# SNES-GamePad.net
KiCad netlist of a schematic drawn in EAGLE
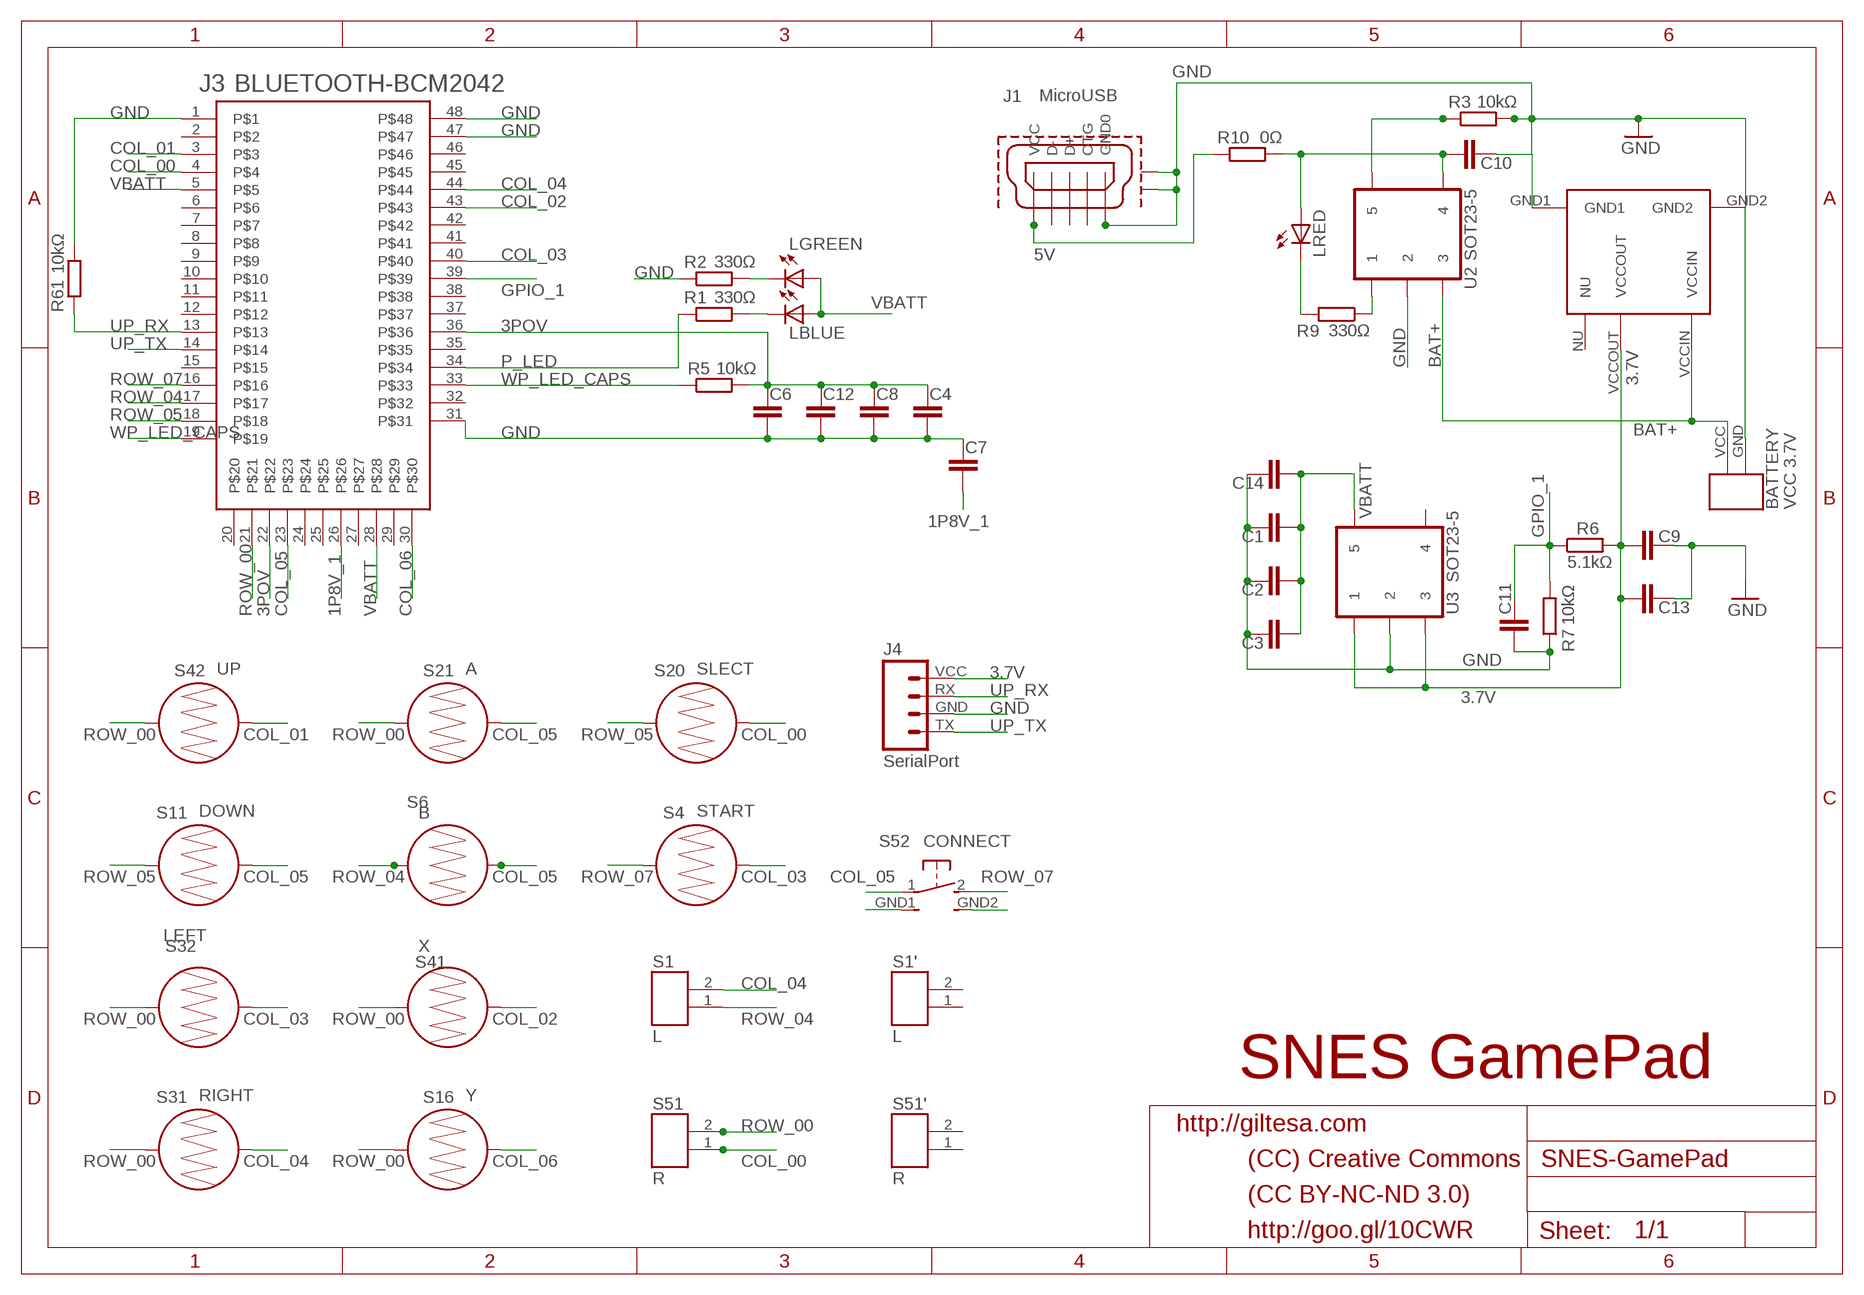
[diagram p0: schematic, sheet 1]

(export (version "E")
  (design (tool "Eeschema 10.0.6"))
  (components
    (comp (ref "BATTERY")
      (value "VCC 3.7V")
      (footprint "eagle-import:1X02_SMD_BIG")
      (libsource (lib "eagle-import") (part "1X02_SMD_BIG"))
    )
    (comp (ref "C1")
      (value "C-EUC0603")
      (footprint "eagle-import:C0603")
      (libsource (lib "eagle-import") (part "C-EUC0603"))
    )
    (comp (ref "C2")
      (value "C-EUC0805")
      (footprint "eagle-import:C0805")
      (libsource (lib "eagle-import") (part "C-EUC0805"))
    )
    (comp (ref "C3")
      (value "C-EUC0805")
      (footprint "eagle-import:C0805")
      (libsource (lib "eagle-import") (part "C-EUC0805"))
    )
    (comp (ref "C4")
      (value "C-EUC0603")
      (footprint "eagle-import:C0603")
      (libsource (lib "eagle-import") (part "C-EUC0603"))
    )
    (comp (ref "C6")
      (value "C-EUC0805")
      (footprint "eagle-import:C0805")
      (libsource (lib "eagle-import") (part "C-EUC0805"))
    )
    (comp (ref "C7")
      (value "C-EUC0805")
      (footprint "eagle-import:C0805")
      (libsource (lib "eagle-import") (part "C-EUC0805"))
    )
    (comp (ref "C8")
      (value "C-EUC0805")
      (footprint "eagle-import:C0805")
      (libsource (lib "eagle-import") (part "C-EUC0805"))
    )
    (comp (ref "C9")
      (value "C-EUC0805")
      (footprint "eagle-import:C0805")
      (libsource (lib "eagle-import") (part "C-EUC0805"))
    )
    (comp (ref "C10")
      (value "C-EUC0603")
      (footprint "eagle-import:C0603")
      (libsource (lib "eagle-import") (part "C-EUC0603"))
    )
    (comp (ref "C11")
      (value "C-EUC0603")
      (footprint "eagle-import:C0603")
      (libsource (lib "eagle-import") (part "C-EUC0603"))
    )
    (comp (ref "C12")
      (value "C-EUC0805")
      (footprint "eagle-import:C0805")
      (libsource (lib "eagle-import") (part "C-EUC0805"))
    )
    (comp (ref "C13")
      (value "C-EUC0805")
      (footprint "eagle-import:C0805")
      (libsource (lib "eagle-import") (part "C-EUC0805"))
    )
    (comp (ref "C14")
      (value "C-EUC0805")
      (footprint "eagle-import:C0805")
      (libsource (lib "eagle-import") (part "C-EUC0805"))
    )
    (comp (ref "J1")
      (value "MicroUSB")
      (footprint "eagle-import:MICRO_USB_1")
      (libsource (lib "eagle-import") (part "MICRO_USB_1"))
    )
    (comp (ref "J2")
      (value "INTERRUPTOR_1")
      (footprint "eagle-import:INTERRUPTOR_1")
      (libsource (lib "eagle-import") (part "INTERRUPTOR_1"))
    )
    (comp (ref "J3")
      (value "BLUETOOTH-BCM2042")
      (footprint "eagle-import:BLUETOOTH-BCM2042")
      (libsource (lib "eagle-import") (part "BLUETOOTH-BCM2042"))
    )
    (comp (ref "J4")
      (value "SerialPort")
      (footprint "eagle-import:ISP_PORT_SNES")
      (libsource (lib "eagle-import") (part "ISP_PORT_SNES"))
    )
    (comp (ref "LBLUE")
      (value "LEDCHIPLED_0805")
      (footprint "eagle-import:CHIPLED_0805")
      (libsource (lib "eagle-import") (part "LEDCHIPLED_0805"))
    )
    (comp (ref "LGREEN")
      (value "LEDCHIPLED_0805")
      (footprint "eagle-import:CHIPLED_0805")
      (libsource (lib "eagle-import") (part "LEDCHIPLED_0805"))
    )
    (comp (ref "LRED")
      (value "LEDCHIPLED_0805")
      (footprint "eagle-import:CHIPLED_0805")
      (libsource (lib "eagle-import") (part "LEDCHIPLED_0805"))
    )
    (comp (ref "R1")
      (value "330Ω")
      (footprint "eagle-import:R0603")
      (libsource (lib "eagle-import") (part "R-EU_R0603"))
    )
    (comp (ref "R2")
      (value "330Ω")
      (footprint "eagle-import:R0603")
      (libsource (lib "eagle-import") (part "R-EU_R0603"))
    )
    (comp (ref "R3")
      (value "10kΩ")
      (footprint "eagle-import:R0603")
      (libsource (lib "eagle-import") (part "R-EU_R0603"))
    )
    (comp (ref "R5")
      (value "10kΩ")
      (footprint "eagle-import:R0603")
      (libsource (lib "eagle-import") (part "R-EU_R0603"))
    )
    (comp (ref "R6")
      (value "5.1kΩ")
      (footprint "eagle-import:R0603")
      (libsource (lib "eagle-import") (part "R-EU_R0603"))
    )
    (comp (ref "R7")
      (value "10kΩ")
      (footprint "eagle-import:R0603")
      (libsource (lib "eagle-import") (part "R-EU_R0603"))
    )
    (comp (ref "R9")
      (value "330Ω")
      (footprint "eagle-import:R0603")
      (libsource (lib "eagle-import") (part "R-EU_R0603"))
    )
    (comp (ref "R10")
      (value "0Ω")
      (footprint "eagle-import:R0603")
      (libsource (lib "eagle-import") (part "R-EU_R0603"))
    )
    (comp (ref "R61")
      (value "10kΩ")
      (footprint "eagle-import:R0603")
      (libsource (lib "eagle-import") (part "R-EU_R0603"))
    )
    (comp (ref "S1")
      (value "L")
      (footprint "eagle-import:1X02_SMD")
      (libsource (lib "eagle-import") (part "1X02_SMD"))
    )
    (comp (ref "S1'")
      (value "L")
      (footprint "eagle-import:SNES_GAMEPAD_RL")
      (libsource (lib "eagle-import") (part "SNES_GAMEPAD_RL"))
    )
    (comp (ref "S4")
      (value "START")
      (footprint "eagle-import:BUTTON-CONDUCTIVE-BUTTON")
      (libsource (lib "eagle-import") (part "BUTTON-CONDUCTIVE-BUTTON"))
    )
    (comp (ref "S6")
      (value "B")
      (footprint "eagle-import:BUTTON-CONDUCTIVE-BUTTON")
      (libsource (lib "eagle-import") (part "BUTTON-CONDUCTIVE-BUTTON"))
    )
    (comp (ref "S11")
      (value "DOWN")
      (footprint "eagle-import:BUTTON-CONDUCTIVE-PAD")
      (libsource (lib "eagle-import") (part "BUTTON-CONDUCTIVE-PAD"))
    )
    (comp (ref "S16")
      (value "Y")
      (footprint "eagle-import:BUTTON-CONDUCTIVE-BUTTON")
      (libsource (lib "eagle-import") (part "BUTTON-CONDUCTIVE-BUTTON"))
    )
    (comp (ref "S20")
      (value "SLECT")
      (footprint "eagle-import:BUTTON-CONDUCTIVE-BUTTON")
      (libsource (lib "eagle-import") (part "BUTTON-CONDUCTIVE-BUTTON"))
    )
    (comp (ref "S21")
      (value "A")
      (footprint "eagle-import:BUTTON-CONDUCTIVE-BUTTON")
      (libsource (lib "eagle-import") (part "BUTTON-CONDUCTIVE-BUTTON"))
    )
    (comp (ref "S31")
      (value "RIGHT")
      (footprint "eagle-import:BUTTON-CONDUCTIVE-PAD")
      (libsource (lib "eagle-import") (part "BUTTON-CONDUCTIVE-PAD"))
    )
    (comp (ref "S32")
      (value "LEFT")
      (footprint "eagle-import:BUTTON-CONDUCTIVE-PAD")
      (libsource (lib "eagle-import") (part "BUTTON-CONDUCTIVE-PAD"))
    )
    (comp (ref "S41")
      (value "X")
      (footprint "eagle-import:BUTTON-CONDUCTIVE-BUTTON")
      (libsource (lib "eagle-import") (part "BUTTON-CONDUCTIVE-BUTTON"))
    )
    (comp (ref "S42")
      (value "UP")
      (footprint "eagle-import:BUTTON-CONDUCTIVE-PAD")
      (libsource (lib "eagle-import") (part "BUTTON-CONDUCTIVE-PAD"))
    )
    (comp (ref "S51")
      (value "R")
      (footprint "eagle-import:1X02_SMD")
      (libsource (lib "eagle-import") (part "1X02_SMD"))
    )
    (comp (ref "S51'")
      (value "R")
      (footprint "eagle-import:SNES_GAMEPAD_RL")
      (libsource (lib "eagle-import") (part "SNES_GAMEPAD_RL"))
    )
    (comp (ref "S52")
      (value "CONNECT")
      (footprint "eagle-import:SWITCH-90º")
      (libsource (lib "eagle-import") (part "SWITCH-90º"))
    )
    (comp (ref "U2")
      (value "SOT23-5")
      (footprint "eagle-import:SOT23-5")
      (libsource (lib "eagle-import") (part "SOT23-5"))
    )
    (comp (ref "U3")
      (value "SOT23-5")
      (footprint "eagle-import:SOT23-5")
      (libsource (lib "eagle-import") (part "SOT23-5"))
    )
  )
  (nets
    (net (code "1") (name "/1P8V_1") (class "Default")
      (node (ref "C7") (pin "1") (pinfunction "1_1") (pintype "passive"))
      (node (ref "J3") (pin "26") (pinfunction "P$26_26") (pintype "bidirectional"))
    )
    (net (code "2") (name "/3.7V") (class "Default")
      (node (ref "C13") (pin "2") (pinfunction "2_2") (pintype "passive"))
      (node (ref "C9") (pin "2") (pinfunction "2_2") (pintype "passive"))
      (node (ref "J2") (pin "VCCOUT") (pinfunction "VCCOUT_VCCOUT") (pintype "bidirectional"))
      (node (ref "J4") (pin "VCC") (pinfunction "VCC_VCC") (pintype "passive"))
      (node (ref "R6") (pin "2") (pinfunction "2_2") (pintype "passive"))
      (node (ref "U3") (pin "1") (pinfunction "1_1") (pintype "input"))
      (node (ref "U3") (pin "3") (pinfunction "3_3") (pintype "input"))
    )
    (net (code "3") (name "/3POV") (class "Default")
      (node (ref "C12") (pin "1") (pinfunction "1_1") (pintype "passive"))
      (node (ref "C4") (pin "1") (pinfunction "1_1") (pintype "passive"))
      (node (ref "C6") (pin "1") (pinfunction "1_1") (pintype "passive"))
      (node (ref "C8") (pin "1") (pinfunction "1_1") (pintype "passive"))
      (node (ref "J3") (pin "22") (pinfunction "P$22_22") (pintype "bidirectional"))
      (node (ref "J3") (pin "36") (pinfunction "P$36_36") (pintype "bidirectional"))
      (node (ref "R5") (pin "2") (pinfunction "2_2") (pintype "passive"))
    )
    (net (code "4") (name "/5V") (class "Default")
      (node (ref "J1") (pin "VCC") (pinfunction "VCC_VCC") (pintype "input"))
      (node (ref "R10") (pin "1") (pinfunction "1_1") (pintype "passive"))
    )
    (net (code "5") (name "/BAT+") (class "Default")
      (node (ref "BATTERY") (pin "VCC") (pinfunction "VCC_VCC") (pintype "passive"))
      (node (ref "J2") (pin "VCCIN") (pinfunction "VCCIN_VCCIN") (pintype "bidirectional"))
      (node (ref "U2") (pin "3") (pinfunction "3_3") (pintype "input"))
    )
    (net (code "6") (name "/COL_00") (class "Default")
      (node (ref "J3") (pin "4") (pinfunction "P$4_4") (pintype "bidirectional"))
      (node (ref "S20") (pin "2") (pinfunction "2_2") (pintype "passive"))
      (node (ref "S51") (pin "1") (pinfunction "1_1") (pintype "passive"))
    )
    (net (code "7") (name "/COL_01") (class "Default")
      (node (ref "J3") (pin "3") (pinfunction "P$3_3") (pintype "bidirectional"))
      (node (ref "S42") (pin "2") (pinfunction "2_2") (pintype "passive"))
    )
    (net (code "8") (name "/COL_02") (class "Default")
      (node (ref "J3") (pin "43") (pinfunction "P$43_43") (pintype "bidirectional"))
      (node (ref "S41") (pin "1") (pinfunction "1_1") (pintype "passive"))
    )
    (net (code "9") (name "/COL_03") (class "Default")
      (node (ref "J3") (pin "40") (pinfunction "P$40_40") (pintype "bidirectional"))
      (node (ref "S32") (pin "1") (pinfunction "1_1") (pintype "passive"))
      (node (ref "S4") (pin "2") (pinfunction "2_2") (pintype "passive"))
    )
    (net (code "10") (name "/COL_04") (class "Default")
      (node (ref "J3") (pin "44") (pinfunction "P$44_44") (pintype "bidirectional"))
      (node (ref "S1") (pin "2") (pinfunction "2_2") (pintype "passive"))
      (node (ref "S31") (pin "2") (pinfunction "2_2") (pintype "passive"))
    )
    (net (code "11") (name "/COL_05") (class "Default")
      (node (ref "J3") (pin "23") (pinfunction "P$23_23") (pintype "bidirectional"))
      (node (ref "S11") (pin "2") (pinfunction "2_2") (pintype "passive"))
      (node (ref "S21") (pin "2") (pinfunction "2_2") (pintype "passive"))
      (node (ref "S52") (pin "1") (pinfunction "1_1") (pintype "passive"))
      (node (ref "S6") (pin "1") (pinfunction "1_1") (pintype "passive"))
    )
    (net (code "12") (name "/COL_06") (class "Default")
      (node (ref "J3") (pin "30") (pinfunction "P$30_30") (pintype "bidirectional"))
      (node (ref "S16") (pin "2") (pinfunction "2_2") (pintype "passive"))
    )
    (net (code "13") (name "/GPIO_1") (class "Default")
      (node (ref "C11") (pin "2") (pinfunction "2_2") (pintype "passive"))
      (node (ref "J3") (pin "39") (pinfunction "P$39_39") (pintype "bidirectional"))
      (node (ref "R6") (pin "1") (pinfunction "1_1") (pintype "passive"))
      (node (ref "R7") (pin "2") (pinfunction "2_2") (pintype "passive"))
    )
    (net (code "14") (name "/P_LED") (class "Default")
      (node (ref "J3") (pin "34") (pinfunction "P$34_34") (pintype "bidirectional"))
      (node (ref "R1") (pin "1") (pinfunction "1_1") (pintype "passive"))
    )
    (net (code "15") (name "/ROW_00") (class "Default")
      (node (ref "J3") (pin "21") (pinfunction "P$21_21") (pintype "bidirectional"))
      (node (ref "S16") (pin "1") (pinfunction "1_1") (pintype "passive"))
      (node (ref "S21") (pin "1") (pinfunction "1_1") (pintype "passive"))
      (node (ref "S31") (pin "1") (pinfunction "1_1") (pintype "passive"))
      (node (ref "S32") (pin "2") (pinfunction "2_2") (pintype "passive"))
      (node (ref "S41") (pin "2") (pinfunction "2_2") (pintype "passive"))
      (node (ref "S42") (pin "1") (pinfunction "1_1") (pintype "passive"))
      (node (ref "S51") (pin "2") (pinfunction "2_2") (pintype "passive"))
    )
    (net (code "16") (name "/ROW_04") (class "Default")
      (node (ref "J3") (pin "17") (pinfunction "P$17_17") (pintype "bidirectional"))
      (node (ref "S1") (pin "1") (pinfunction "1_1") (pintype "passive"))
      (node (ref "S6") (pin "2") (pinfunction "2_2") (pintype "passive"))
    )
    (net (code "17") (name "/ROW_05") (class "Default")
      (node (ref "J3") (pin "18") (pinfunction "P$18_18") (pintype "bidirectional"))
      (node (ref "S11") (pin "1") (pinfunction "1_1") (pintype "passive"))
      (node (ref "S20") (pin "1") (pinfunction "1_1") (pintype "passive"))
    )
    (net (code "18") (name "/ROW_07") (class "Default")
      (node (ref "J3") (pin "16") (pinfunction "P$16_16") (pintype "bidirectional"))
      (node (ref "S4") (pin "1") (pinfunction "1_1") (pintype "passive"))
      (node (ref "S52") (pin "2") (pinfunction "2_2") (pintype "passive"))
    )
    (net (code "19") (name "/UP_RX") (class "Default")
      (node (ref "J3") (pin "13") (pinfunction "P$13_13") (pintype "bidirectional"))
      (node (ref "J4") (pin "RX") (pinfunction "RX_RX") (pintype "passive"))
      (node (ref "R61") (pin "1") (pinfunction "1_1") (pintype "passive"))
    )
    (net (code "20") (name "/UP_TX") (class "Default")
      (node (ref "J3") (pin "14") (pinfunction "P$14_14") (pintype "bidirectional"))
      (node (ref "J4") (pin "TX") (pinfunction "TX_TX") (pintype "passive"))
    )
    (net (code "21") (name "/VBATT") (class "Default")
      (node (ref "C1") (pin "2") (pinfunction "2_2") (pintype "passive"))
      (node (ref "C14") (pin "2") (pinfunction "2_2") (pintype "passive"))
      (node (ref "C2") (pin "2") (pinfunction "2_2") (pintype "passive"))
      (node (ref "C3") (pin "2") (pinfunction "2_2") (pintype "passive"))
      (node (ref "J3") (pin "28") (pinfunction "P$28_28") (pintype "bidirectional"))
      (node (ref "J3") (pin "5") (pinfunction "P$5_5") (pintype "bidirectional"))
      (node (ref "LBLUE") (pin "A") (pinfunction "A_A") (pintype "passive"))
      (node (ref "LGREEN") (pin "A") (pinfunction "A_A") (pintype "passive"))
      (node (ref "U3") (pin "5") (pinfunction "5_5") (pintype "passive"))
    )
    (net (code "22") (name "/WP_LED_CAPS") (class "Default")
      (node (ref "J3") (pin "19") (pinfunction "P$19_19") (pintype "bidirectional"))
      (node (ref "J3") (pin "33") (pinfunction "P$33_33") (pintype "bidirectional"))
      (node (ref "R5") (pin "1") (pinfunction "1_1") (pintype "passive"))
    )
    (net (code "23") (name "GND") (class "Default")
      (node (ref "BATTERY") (pin "GND") (pinfunction "GND_GND") (pintype "passive"))
      (node (ref "C1") (pin "1") (pinfunction "1_1") (pintype "passive"))
      (node (ref "C10") (pin "2") (pinfunction "2_2") (pintype "passive"))
      (node (ref "C11") (pin "1") (pinfunction "1_1") (pintype "passive"))
      (node (ref "C12") (pin "2") (pinfunction "2_2") (pintype "passive"))
      (node (ref "C13") (pin "1") (pinfunction "1_1") (pintype "passive"))
      (node (ref "C14") (pin "1") (pinfunction "1_1") (pintype "passive"))
      (node (ref "C2") (pin "1") (pinfunction "1_1") (pintype "passive"))
      (node (ref "C3") (pin "1") (pinfunction "1_1") (pintype "passive"))
      (node (ref "C4") (pin "2") (pinfunction "2_2") (pintype "passive"))
      (node (ref "C6") (pin "2") (pinfunction "2_2") (pintype "passive"))
      (node (ref "C7") (pin "2") (pinfunction "2_2") (pintype "passive"))
      (node (ref "C8") (pin "2") (pinfunction "2_2") (pintype "passive"))
      (node (ref "C9") (pin "1") (pinfunction "1_1") (pintype "passive"))
      (node (ref "J1") (pin "GND0") (pinfunction "GND0_GND0") (pintype "input"))
      (node (ref "J1") (pin "GND1") (pinfunction "GND1_GND1") (pintype "bidirectional"))
      (node (ref "J1") (pin "GND2") (pinfunction "GND2_GND2") (pintype "bidirectional"))
      (node (ref "J2") (pin "GND1") (pinfunction "GND1_GND1") (pintype "bidirectional"))
      (node (ref "J2") (pin "GND2") (pinfunction "GND2_GND2") (pintype "bidirectional"))
      (node (ref "J3") (pin "1") (pinfunction "P$1_1") (pintype "bidirectional"))
      (node (ref "J3") (pin "31") (pinfunction "P$31_31") (pintype "bidirectional"))
      (node (ref "J3") (pin "47") (pinfunction "P$47_47") (pintype "bidirectional"))
      (node (ref "J3") (pin "48") (pinfunction "P$48_48") (pintype "bidirectional"))
      (node (ref "J4") (pin "GND") (pinfunction "GND_GND") (pintype "passive"))
      (node (ref "R2") (pin "1") (pinfunction "1_1") (pintype "passive"))
      (node (ref "R3") (pin "2") (pinfunction "2_2") (pintype "passive"))
      (node (ref "R61") (pin "2") (pinfunction "2_2") (pintype "passive"))
      (node (ref "R7") (pin "1") (pinfunction "1_1") (pintype "passive"))
      (node (ref "S52") (pin "GND1") (pinfunction "GND1_GND1") (pintype "passive"))
      (node (ref "S52") (pin "GND2") (pinfunction "GND2_GND2") (pintype "passive"))
      (node (ref "U2") (pin "2") (pinfunction "2_2") (pintype "input"))
      (node (ref "U3") (pin "2") (pinfunction "2_2") (pintype "input"))
    )
    (net (code "24") (name "Net-(C10-Pad1)") (class "Default")
      (node (ref "C10") (pin "1") (pinfunction "1_1") (pintype "passive"))
      (node (ref "LRED") (pin "A") (pinfunction "A_A") (pintype "passive"))
      (node (ref "R10") (pin "2") (pinfunction "2_2") (pintype "passive"))
      (node (ref "U2") (pin "4") (pinfunction "4_4") (pintype "input"))
    )
    (net (code "25") (name "Net-(LBLUE-PadC)") (class "Default")
      (node (ref "LBLUE") (pin "C") (pinfunction "C_C") (pintype "passive"))
      (node (ref "R1") (pin "2") (pinfunction "2_2") (pintype "passive"))
    )
    (net (code "26") (name "Net-(LGREEN-PadC)") (class "Default")
      (node (ref "LGREEN") (pin "C") (pinfunction "C_C") (pintype "passive"))
      (node (ref "R2") (pin "2") (pinfunction "2_2") (pintype "passive"))
    )
    (net (code "27") (name "Net-(LRED-PadC)") (class "Default")
      (node (ref "LRED") (pin "C") (pinfunction "C_C") (pintype "passive"))
      (node (ref "R9") (pin "2") (pinfunction "2_2") (pintype "passive"))
    )
    (net (code "28") (name "Net-(R3-Pad1)") (class "Default")
      (node (ref "R3") (pin "1") (pinfunction "1_1") (pintype "passive"))
      (node (ref "U2") (pin "5") (pinfunction "5_5") (pintype "passive"))
    )
    (net (code "29") (name "Net-(R9-Pad1)") (class "Default")
      (node (ref "R9") (pin "1") (pinfunction "1_1") (pintype "passive"))
      (node (ref "U2") (pin "1") (pinfunction "1_1") (pintype "input"))
    )
    (net (code "30") (name "unconnected-(J1-PadD+)") (class "Default")
      (node (ref "J1") (pin "D+") (pinfunction "D+_D+") (pintype "input"))
    )
    (net (code "31") (name "unconnected-(J1-PadD-)") (class "Default")
      (node (ref "J1") (pin "D-") (pinfunction "D-_D-") (pintype "input"))
    )
    (net (code "32") (name "unconnected-(J1-PadOTG)") (class "Default")
      (node (ref "J1") (pin "OTG") (pinfunction "OTG_OTG") (pintype "input"))
    )
    (net (code "33") (name "unconnected-(J2-PadNU)") (class "Default")
      (node (ref "J2") (pin "NU") (pinfunction "NU_NU") (pintype "bidirectional"))
    )
    (net (code "34") (name "unconnected-(J3-P$2-Pad2)") (class "Default")
      (node (ref "J3") (pin "2") (pinfunction "P$2_2") (pintype "bidirectional"))
    )
    (net (code "35") (name "unconnected-(J3-P$6-Pad6)") (class "Default")
      (node (ref "J3") (pin "6") (pinfunction "P$6_6") (pintype "bidirectional"))
    )
    (net (code "36") (name "unconnected-(J3-P$7-Pad7)") (class "Default")
      (node (ref "J3") (pin "7") (pinfunction "P$7_7") (pintype "bidirectional"))
    )
    (net (code "37") (name "unconnected-(J3-P$8-Pad8)") (class "Default")
      (node (ref "J3") (pin "8") (pinfunction "P$8_8") (pintype "bidirectional"))
    )
    (net (code "38") (name "unconnected-(J3-P$9-Pad9)") (class "Default")
      (node (ref "J3") (pin "9") (pinfunction "P$9_9") (pintype "bidirectional"))
    )
    (net (code "39") (name "unconnected-(J3-P$10-Pad10)") (class "Default")
      (node (ref "J3") (pin "10") (pinfunction "P$10_10") (pintype "bidirectional"))
    )
    (net (code "40") (name "unconnected-(J3-P$11-Pad11)") (class "Default")
      (node (ref "J3") (pin "11") (pinfunction "P$11_11") (pintype "bidirectional"))
    )
    (net (code "41") (name "unconnected-(J3-P$12-Pad12)") (class "Default")
      (node (ref "J3") (pin "12") (pinfunction "P$12_12") (pintype "bidirectional"))
    )
    (net (code "42") (name "unconnected-(J3-P$15-Pad15)") (class "Default")
      (node (ref "J3") (pin "15") (pinfunction "P$15_15") (pintype "bidirectional"))
    )
    (net (code "43") (name "unconnected-(J3-P$20-Pad20)") (class "Default")
      (node (ref "J3") (pin "20") (pinfunction "P$20_20") (pintype "bidirectional"))
    )
    (net (code "44") (name "unconnected-(J3-P$24-Pad24)") (class "Default")
      (node (ref "J3") (pin "24") (pinfunction "P$24_24") (pintype "bidirectional"))
    )
    (net (code "45") (name "unconnected-(J3-P$25-Pad25)") (class "Default")
      (node (ref "J3") (pin "25") (pinfunction "P$25_25") (pintype "bidirectional"))
    )
    (net (code "46") (name "unconnected-(J3-P$27-Pad27)") (class "Default")
      (node (ref "J3") (pin "27") (pinfunction "P$27_27") (pintype "bidirectional"))
    )
    (net (code "47") (name "unconnected-(J3-P$29-Pad29)") (class "Default")
      (node (ref "J3") (pin "29") (pinfunction "P$29_29") (pintype "bidirectional"))
    )
    (net (code "48") (name "unconnected-(J3-P$32-Pad32)") (class "Default")
      (node (ref "J3") (pin "32") (pinfunction "P$32_32") (pintype "bidirectional"))
    )
    (net (code "49") (name "unconnected-(J3-P$35-Pad35)") (class "Default")
      (node (ref "J3") (pin "35") (pinfunction "P$35_35") (pintype "bidirectional"))
    )
    (net (code "50") (name "unconnected-(J3-P$37-Pad37)") (class "Default")
      (node (ref "J3") (pin "37") (pinfunction "P$37_37") (pintype "bidirectional"))
    )
    (net (code "51") (name "unconnected-(J3-P$38-Pad38)") (class "Default")
      (node (ref "J3") (pin "38") (pinfunction "P$38_38") (pintype "bidirectional"))
    )
    (net (code "52") (name "unconnected-(J3-P$41-Pad41)") (class "Default")
      (node (ref "J3") (pin "41") (pinfunction "P$41_41") (pintype "bidirectional"))
    )
    (net (code "53") (name "unconnected-(J3-P$42-Pad42)") (class "Default")
      (node (ref "J3") (pin "42") (pinfunction "P$42_42") (pintype "bidirectional"))
    )
    (net (code "54") (name "unconnected-(J3-P$45-Pad45)") (class "Default")
      (node (ref "J3") (pin "45") (pinfunction "P$45_45") (pintype "bidirectional"))
    )
    (net (code "55") (name "unconnected-(J3-P$46-Pad46)") (class "Default")
      (node (ref "J3") (pin "46") (pinfunction "P$46_46") (pintype "bidirectional"))
    )
    (net (code "56") (name "unconnected-(S1'-Pad1)") (class "Default")
      (node (ref "S1'") (pin "1") (pinfunction "1_1") (pintype "passive"))
    )
    (net (code "57") (name "unconnected-(S1'-Pad2)") (class "Default")
      (node (ref "S1'") (pin "2") (pinfunction "2_2") (pintype "passive"))
    )
    (net (code "58") (name "unconnected-(S51'-Pad1)") (class "Default")
      (node (ref "S51'") (pin "1") (pinfunction "1_1") (pintype "passive"))
    )
    (net (code "59") (name "unconnected-(S51'-Pad2)") (class "Default")
      (node (ref "S51'") (pin "2") (pinfunction "2_2") (pintype "passive"))
    )
    (net (code "60") (name "unconnected-(U3-Pad4)") (class "Default")
      (node (ref "U3") (pin "4") (pinfunction "4_4") (pintype "input"))
    )
  )
)
